# MC21R01_uC_GPIO.net
KiCad netlist of a schematic drawn in Altium Designer
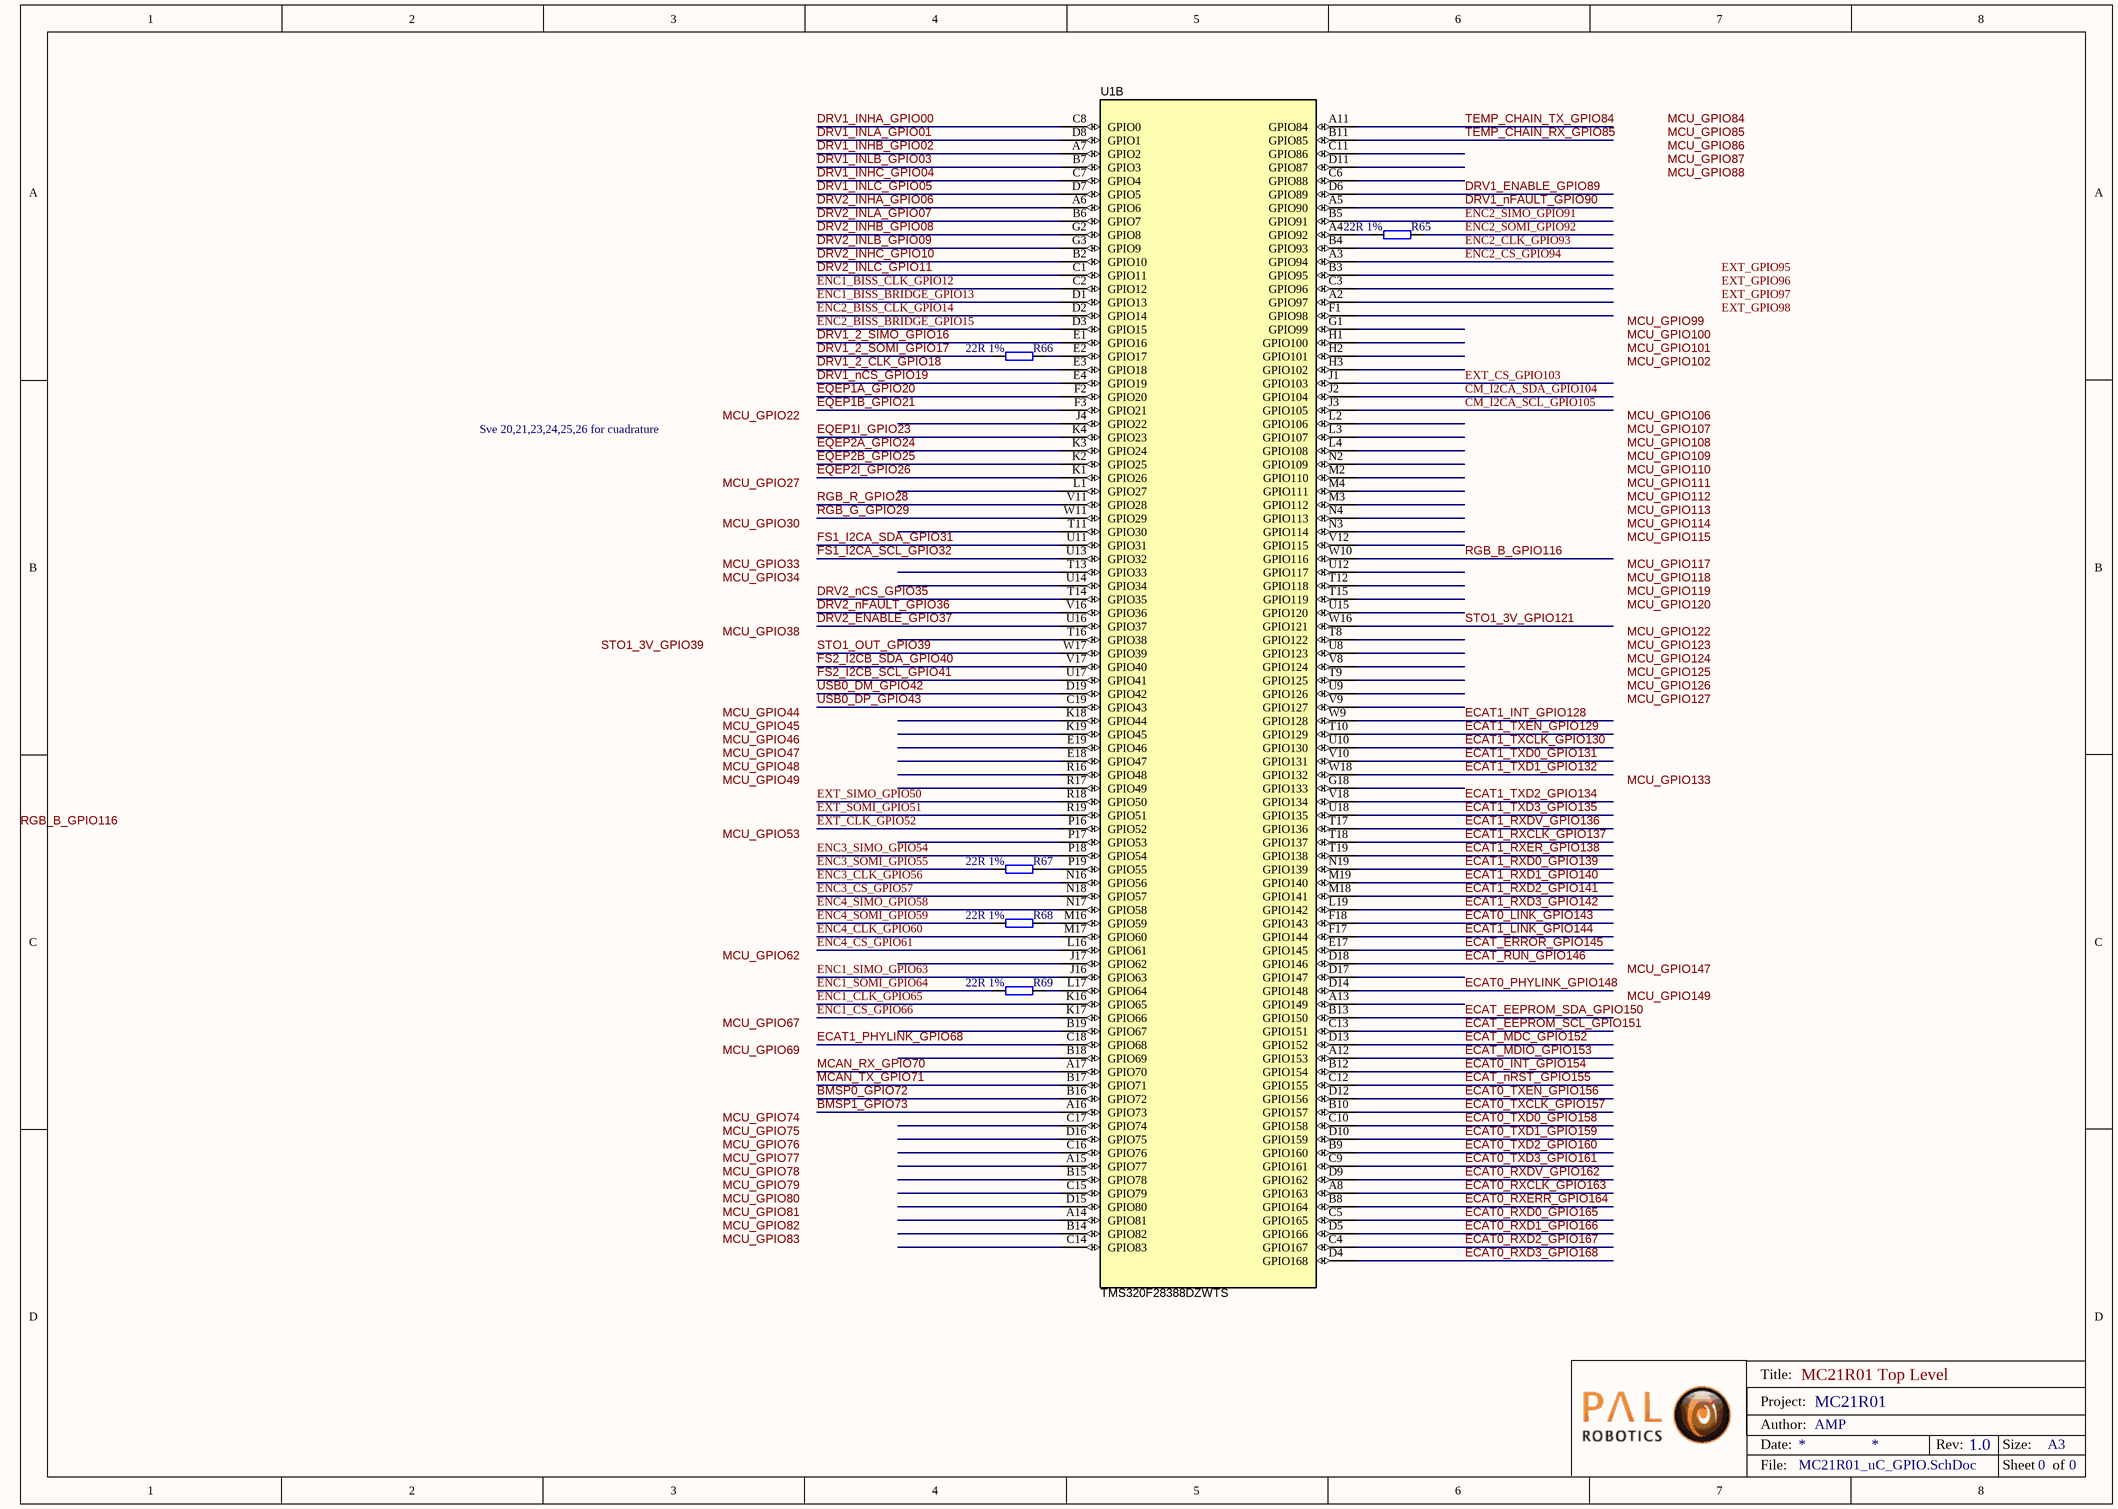
[diagram p0: MC21R01_uC_GPIO.SchDoc]

(export (version "E")
  (design (tool "Eeschema 10.0.6"))
  (components
    (comp (ref "R65")
      (value "22R 1%")
      (footprint "0402 SMD rESISTOR")
      (description "22R/50V 1% 0402 63mW SMD Resistor")
      (libsource (lib "PAL_Resistors") (part "22R/50V 1% 0402 63mW"))
    )
    (comp (ref "R66")
      (value "22R 1%")
      (footprint "0402 SMD rESISTOR")
      (description "22R/50V 1% 0402 63mW SMD Resistor")
      (libsource (lib "PAL_Resistors") (part "22R/50V 1% 0402 63mW"))
    )
    (comp (ref "R67")
      (value "22R 1%")
      (footprint "0402 SMD rESISTOR")
      (description "22R/50V 1% 0402 63mW SMD Resistor")
      (libsource (lib "PAL_Resistors") (part "22R/50V 1% 0402 63mW"))
    )
    (comp (ref "R68")
      (value "22R 1%")
      (footprint "0402 SMD rESISTOR")
      (description "22R/50V 1% 0402 63mW SMD Resistor")
      (libsource (lib "PAL_Resistors") (part "22R/50V 1% 0402 63mW"))
    )
    (comp (ref "R69")
      (value "22R 1%")
      (footprint "0402 SMD rESISTOR")
      (description "22R/50V 1% 0402 63mW SMD Resistor")
      (libsource (lib "PAL_Resistors") (part "22R/50V 1% 0402 63mW"))
    )
    (comp (ref "U1")
      (value "TMS320F28388DZWTS")
      (footprint "ZWT0337A")
      (description "TMS320F28388DZWTS, ZWT0337A (NFBGA-337)")
      (fields
        (field (name "MANUFACTURER") "Texas Instruments")
        (field (name "PARTNUMBER") "TMS320F28388DZWTS")
      )
      (libsource (lib "PAL_devices") (part "TMS320F28388"))
    )
  )
  (nets
    (net (code "1") (name "/BMSP0_GPIO72") (class "Default")
      (node (ref "U1") (pin "B16") (pinfunction "GPIO72_B16") (pintype "bidirectional"))
    )
    (net (code "2") (name "/BMSP1_GPIO73") (class "Default")
      (node (ref "U1") (pin "A16") (pinfunction "GPIO73_A16") (pintype "bidirectional"))
    )
    (net (code "3") (name "/CM_I2CA_SCL_GPIO105") (class "Default")
      (node (ref "U1") (pin "J3") (pinfunction "GPIO105_J3") (pintype "bidirectional"))
    )
    (net (code "4") (name "/CM_I2CA_SDA_GPIO104") (class "Default")
      (node (ref "U1") (pin "J2") (pinfunction "GPIO104_J2") (pintype "bidirectional"))
    )
    (net (code "5") (name "/DRV1_2_CLK_GPIO18") (class "Default")
      (node (ref "U1") (pin "E3") (pinfunction "GPIO18_E3") (pintype "bidirectional"))
    )
    (net (code "6") (name "/DRV1_2_SIMO_GPIO16") (class "Default")
      (node (ref "U1") (pin "E1") (pinfunction "GPIO16_E1") (pintype "bidirectional"))
    )
    (net (code "7") (name "/DRV1_2_SOMI_GPIO17") (class "Default")
      (node (ref "R66") (pin "2") (pinfunction "2_2") (pintype "passive"))
    )
    (net (code "8") (name "/DRV1_ENABLE_GPIO89") (class "Default")
      (node (ref "U1") (pin "D6") (pinfunction "GPIO89_D6") (pintype "bidirectional"))
    )
    (net (code "9") (name "/DRV1_INHA_GPIO00") (class "Default")
      (node (ref "U1") (pin "C8") (pinfunction "GPIO0_C8") (pintype "bidirectional"))
    )
    (net (code "10") (name "/DRV1_INHB_GPIO02") (class "Default")
      (node (ref "U1") (pin "A7") (pinfunction "GPIO2_A7") (pintype "bidirectional"))
    )
    (net (code "11") (name "/DRV1_INHC_GPIO04") (class "Default")
      (node (ref "U1") (pin "C7") (pinfunction "GPIO4_C7") (pintype "bidirectional"))
    )
    (net (code "12") (name "/DRV1_INLA_GPIO01") (class "Default")
      (node (ref "U1") (pin "D8") (pinfunction "GPIO1_D8") (pintype "bidirectional"))
    )
    (net (code "13") (name "/DRV1_INLB_GPIO03") (class "Default")
      (node (ref "U1") (pin "B7") (pinfunction "GPIO3_B7") (pintype "bidirectional"))
    )
    (net (code "14") (name "/DRV1_INLC_GPIO05") (class "Default")
      (node (ref "U1") (pin "D7") (pinfunction "GPIO5_D7") (pintype "bidirectional"))
    )
    (net (code "15") (name "/DRV1_nCS_GPIO19") (class "Default")
      (node (ref "U1") (pin "E4") (pinfunction "GPIO19_E4") (pintype "bidirectional"))
    )
    (net (code "16") (name "/DRV1_nFAULT_GPIO90") (class "Default")
      (node (ref "U1") (pin "A5") (pinfunction "GPIO90_A5") (pintype "bidirectional"))
    )
    (net (code "17") (name "/DRV2_ENABLE_GPIO37") (class "Default")
      (node (ref "U1") (pin "U16") (pinfunction "GPIO37_U16") (pintype "bidirectional"))
    )
    (net (code "18") (name "/DRV2_INHA_GPIO06") (class "Default")
      (node (ref "U1") (pin "A6") (pinfunction "GPIO6_A6") (pintype "bidirectional"))
    )
    (net (code "19") (name "/DRV2_INHB_GPIO08") (class "Default")
      (node (ref "U1") (pin "G2") (pinfunction "GPIO8_G2") (pintype "bidirectional"))
    )
    (net (code "20") (name "/DRV2_INHC_GPIO10") (class "Default")
      (node (ref "U1") (pin "B2") (pinfunction "GPIO10_B2") (pintype "bidirectional"))
    )
    (net (code "21") (name "/DRV2_INLA_GPIO07") (class "Default")
      (node (ref "U1") (pin "B6") (pinfunction "GPIO7_B6") (pintype "bidirectional"))
    )
    (net (code "22") (name "/DRV2_INLB_GPIO09") (class "Default")
      (node (ref "U1") (pin "G3") (pinfunction "GPIO9_G3") (pintype "bidirectional"))
    )
    (net (code "23") (name "/DRV2_INLC_GPIO11") (class "Default")
      (node (ref "U1") (pin "C1") (pinfunction "GPIO11_C1") (pintype "bidirectional"))
    )
    (net (code "24") (name "/DRV2_nCS_GPIO35") (class "Default")
      (node (ref "U1") (pin "T14") (pinfunction "GPIO35_T14") (pintype "bidirectional"))
    )
    (net (code "25") (name "/DRV2_nFAULT_GPIO36") (class "Default")
      (node (ref "U1") (pin "V16") (pinfunction "GPIO36_V16") (pintype "bidirectional"))
    )
    (net (code "26") (name "/ECAT0_INT_GPIO154") (class "Default")
      (node (ref "U1") (pin "B12") (pinfunction "GPIO154_B12") (pintype "bidirectional"))
    )
    (net (code "27") (name "/ECAT0_LINK_GPIO143") (class "Default")
      (node (ref "U1") (pin "F18") (pinfunction "GPIO143_F18") (pintype "bidirectional"))
    )
    (net (code "28") (name "/ECAT0_PHYLINK_GPIO148") (class "Default")
      (node (ref "U1") (pin "D14") (pinfunction "GPIO148_D14") (pintype "bidirectional"))
    )
    (net (code "29") (name "/ECAT0_RXCLK_GPIO163") (class "Default")
      (node (ref "U1") (pin "A8") (pinfunction "GPIO163_A8") (pintype "bidirectional"))
    )
    (net (code "30") (name "/ECAT0_RXD0_GPIO165") (class "Default")
      (node (ref "U1") (pin "C5") (pinfunction "GPIO165_C5") (pintype "bidirectional"))
    )
    (net (code "31") (name "/ECAT0_RXD1_GPIO166") (class "Default")
      (node (ref "U1") (pin "D5") (pinfunction "GPIO166_D5") (pintype "bidirectional"))
    )
    (net (code "32") (name "/ECAT0_RXD2_GPIO167") (class "Default")
      (node (ref "U1") (pin "C4") (pinfunction "GPIO167_C4") (pintype "bidirectional"))
    )
    (net (code "33") (name "/ECAT0_RXD3_GPIO168") (class "Default")
      (node (ref "U1") (pin "D4") (pinfunction "GPIO168_D4") (pintype "bidirectional"))
    )
    (net (code "34") (name "/ECAT0_RXDV_GPIO162") (class "Default")
      (node (ref "U1") (pin "D9") (pinfunction "GPIO162_D9") (pintype "bidirectional"))
    )
    (net (code "35") (name "/ECAT0_RXERR_GPIO164") (class "Default")
      (node (ref "U1") (pin "B8") (pinfunction "GPIO164_B8") (pintype "bidirectional"))
    )
    (net (code "36") (name "/ECAT0_TXCLK_GPIO157") (class "Default")
      (node (ref "U1") (pin "B10") (pinfunction "GPIO157_B10") (pintype "bidirectional"))
    )
    (net (code "37") (name "/ECAT0_TXD0_GPIO158") (class "Default")
      (node (ref "U1") (pin "C10") (pinfunction "GPIO158_C10") (pintype "bidirectional"))
    )
    (net (code "38") (name "/ECAT0_TXD1_GPIO159") (class "Default")
      (node (ref "U1") (pin "D10") (pinfunction "GPIO159_D10") (pintype "bidirectional"))
    )
    (net (code "39") (name "/ECAT0_TXD2_GPIO160") (class "Default")
      (node (ref "U1") (pin "B9") (pinfunction "GPIO160_B9") (pintype "bidirectional"))
    )
    (net (code "40") (name "/ECAT0_TXD3_GPIO161") (class "Default")
      (node (ref "U1") (pin "C9") (pinfunction "GPIO161_C9") (pintype "bidirectional"))
    )
    (net (code "41") (name "/ECAT0_TXEN_GPIO156") (class "Default")
      (node (ref "U1") (pin "D12") (pinfunction "GPIO156_D12") (pintype "bidirectional"))
    )
    (net (code "42") (name "/ECAT1_INT_GPIO128") (class "Default")
      (node (ref "U1") (pin "W9") (pinfunction "GPIO128_W9") (pintype "bidirectional"))
    )
    (net (code "43") (name "/ECAT1_LINK_GPIO144") (class "Default")
      (node (ref "U1") (pin "F17") (pinfunction "GPIO144_F17") (pintype "bidirectional"))
    )
    (net (code "44") (name "/ECAT1_PHYLINK_GPIO68") (class "Default")
      (node (ref "U1") (pin "C18") (pinfunction "GPIO68_C18") (pintype "bidirectional"))
    )
    (net (code "45") (name "/ECAT1_RXCLK_GPIO137") (class "Default")
      (node (ref "U1") (pin "T18") (pinfunction "GPIO137_T18") (pintype "bidirectional"))
    )
    (net (code "46") (name "/ECAT1_RXD0_GPIO139") (class "Default")
      (node (ref "U1") (pin "N19") (pinfunction "GPIO139_N19") (pintype "bidirectional"))
    )
    (net (code "47") (name "/ECAT1_RXD1_GPIO140") (class "Default")
      (node (ref "U1") (pin "M19") (pinfunction "GPIO140_M19") (pintype "bidirectional"))
    )
    (net (code "48") (name "/ECAT1_RXD2_GPIO141") (class "Default")
      (node (ref "U1") (pin "M18") (pinfunction "GPIO141_M18") (pintype "bidirectional"))
    )
    (net (code "49") (name "/ECAT1_RXD3_GPIO142") (class "Default")
      (node (ref "U1") (pin "L19") (pinfunction "GPIO142_L19") (pintype "bidirectional"))
    )
    (net (code "50") (name "/ECAT1_RXDV_GPIO136") (class "Default")
      (node (ref "U1") (pin "T17") (pinfunction "GPIO136_T17") (pintype "bidirectional"))
    )
    (net (code "51") (name "/ECAT1_RXER_GPIO138") (class "Default")
      (node (ref "U1") (pin "T19") (pinfunction "GPIO138_T19") (pintype "bidirectional"))
    )
    (net (code "52") (name "/ECAT1_TXCLK_GPIO130") (class "Default")
      (node (ref "U1") (pin "U10") (pinfunction "GPIO130_U10") (pintype "bidirectional"))
    )
    (net (code "53") (name "/ECAT1_TXD0_GPIO131") (class "Default")
      (node (ref "U1") (pin "V10") (pinfunction "GPIO131_V10") (pintype "bidirectional"))
    )
    (net (code "54") (name "/ECAT1_TXD1_GPIO132") (class "Default")
      (node (ref "U1") (pin "W18") (pinfunction "GPIO132_W18") (pintype "bidirectional"))
    )
    (net (code "55") (name "/ECAT1_TXD2_GPIO134") (class "Default")
      (node (ref "U1") (pin "V18") (pinfunction "GPIO134_V18") (pintype "bidirectional"))
    )
    (net (code "56") (name "/ECAT1_TXD3_GPIO135") (class "Default")
      (node (ref "U1") (pin "U18") (pinfunction "GPIO135_U18") (pintype "bidirectional"))
    )
    (net (code "57") (name "/ECAT1_TXEN_GPIO129") (class "Default")
      (node (ref "U1") (pin "T10") (pinfunction "GPIO129_T10") (pintype "bidirectional"))
    )
    (net (code "58") (name "/ECAT_EEPROM_SCL_GPIO151") (class "Default")
      (node (ref "U1") (pin "C13") (pinfunction "GPIO151_C13") (pintype "bidirectional"))
    )
    (net (code "59") (name "/ECAT_EEPROM_SDA_GPIO150") (class "Default")
      (node (ref "U1") (pin "B13") (pinfunction "GPIO150_B13") (pintype "bidirectional"))
    )
    (net (code "60") (name "/ECAT_ERROR_GPIO145") (class "Default")
      (node (ref "U1") (pin "E17") (pinfunction "GPIO145_E17") (pintype "bidirectional"))
    )
    (net (code "61") (name "/ECAT_MDC_GPIO152") (class "Default")
      (node (ref "U1") (pin "D13") (pinfunction "GPIO152_D13") (pintype "bidirectional"))
    )
    (net (code "62") (name "/ECAT_MDIO_GPIO153") (class "Default")
      (node (ref "U1") (pin "A12") (pinfunction "GPIO153_A12") (pintype "bidirectional"))
    )
    (net (code "63") (name "/ECAT_RUN_GPIO146") (class "Default")
      (node (ref "U1") (pin "D18") (pinfunction "GPIO146_D18") (pintype "bidirectional"))
    )
    (net (code "64") (name "/ECAT_nRST_GPIO155") (class "Default")
      (node (ref "U1") (pin "C12") (pinfunction "GPIO155_C12") (pintype "bidirectional"))
    )
    (net (code "65") (name "/ENC1_BISS_BRIDGE_GPIO13") (class "Default")
      (node (ref "U1") (pin "D1") (pinfunction "GPIO13_D1") (pintype "bidirectional"))
    )
    (net (code "66") (name "/ENC1_BISS_CLK_GPIO12") (class "Default")
      (node (ref "U1") (pin "C2") (pinfunction "GPIO12_C2") (pintype "bidirectional"))
    )
    (net (code "67") (name "/ENC1_CLK_GPIO65") (class "Default")
      (node (ref "U1") (pin "K16") (pinfunction "GPIO65_K16") (pintype "bidirectional"))
    )
    (net (code "68") (name "/ENC1_CS_GPIO66") (class "Default")
      (node (ref "U1") (pin "K17") (pinfunction "GPIO66_K17") (pintype "bidirectional"))
    )
    (net (code "69") (name "/ENC1_SIMO_GPIO63") (class "Default")
      (node (ref "U1") (pin "J16") (pinfunction "GPIO63_J16") (pintype "bidirectional"))
    )
    (net (code "70") (name "/ENC1_SOMI_GPIO64") (class "Default")
      (node (ref "R69") (pin "2") (pinfunction "2_2") (pintype "passive"))
    )
    (net (code "71") (name "/ENC2_BISS_BRIDGE_GPIO15") (class "Default")
      (node (ref "U1") (pin "D3") (pinfunction "GPIO15_D3") (pintype "bidirectional"))
    )
    (net (code "72") (name "/ENC2_BISS_CLK_GPIO14") (class "Default")
      (node (ref "U1") (pin "D2") (pinfunction "GPIO14_D2") (pintype "bidirectional"))
    )
    (net (code "73") (name "/ENC2_CLK_GPIO93") (class "Default")
      (node (ref "U1") (pin "B4") (pinfunction "GPIO93_B4") (pintype "bidirectional"))
    )
    (net (code "74") (name "/ENC2_CS_GPIO94") (class "Default")
      (node (ref "U1") (pin "A3") (pinfunction "GPIO94_A3") (pintype "bidirectional"))
    )
    (net (code "75") (name "/ENC2_SIMO_GPIO91") (class "Default")
      (node (ref "U1") (pin "B5") (pinfunction "GPIO91_B5") (pintype "bidirectional"))
    )
    (net (code "76") (name "/ENC2_SOMI_GPIO92") (class "Default")
      (node (ref "R65") (pin "1") (pinfunction "1_1") (pintype "passive"))
    )
    (net (code "77") (name "/ENC3_CLK_GPIO56") (class "Default")
      (node (ref "U1") (pin "N16") (pinfunction "GPIO56_N16") (pintype "bidirectional"))
    )
    (net (code "78") (name "/ENC3_CS_GPIO57") (class "Default")
      (node (ref "U1") (pin "N18") (pinfunction "GPIO57_N18") (pintype "bidirectional"))
    )
    (net (code "79") (name "/ENC3_SIMO_GPIO54") (class "Default")
      (node (ref "U1") (pin "P18") (pinfunction "GPIO54_P18") (pintype "bidirectional"))
    )
    (net (code "80") (name "/ENC3_SOMI_GPIO55") (class "Default")
      (node (ref "R67") (pin "2") (pinfunction "2_2") (pintype "passive"))
    )
    (net (code "81") (name "/ENC4_CLK_GPIO60") (class "Default")
      (node (ref "U1") (pin "M17") (pinfunction "GPIO60_M17") (pintype "bidirectional"))
    )
    (net (code "82") (name "/ENC4_CS_GPIO61") (class "Default")
      (node (ref "U1") (pin "L16") (pinfunction "GPIO61_L16") (pintype "bidirectional"))
    )
    (net (code "83") (name "/ENC4_SIMO_GPIO58") (class "Default")
      (node (ref "U1") (pin "N17") (pinfunction "GPIO58_N17") (pintype "bidirectional"))
    )
    (net (code "84") (name "/ENC4_SOMI_GPIO59") (class "Default")
      (node (ref "R68") (pin "2") (pinfunction "2_2") (pintype "passive"))
    )
    (net (code "85") (name "/EQEP1A_GPIO20") (class "Default")
      (node (ref "U1") (pin "F2") (pinfunction "GPIO20_F2") (pintype "bidirectional"))
    )
    (net (code "86") (name "/EQEP1B_GPIO21") (class "Default")
      (node (ref "U1") (pin "F3") (pinfunction "GPIO21_F3") (pintype "bidirectional"))
    )
    (net (code "87") (name "/EQEP1I_GPIO23") (class "Default")
      (node (ref "U1") (pin "K4") (pinfunction "GPIO23_K4") (pintype "bidirectional"))
    )
    (net (code "88") (name "/EQEP2A_GPIO24") (class "Default")
      (node (ref "U1") (pin "K3") (pinfunction "GPIO24_K3") (pintype "bidirectional"))
    )
    (net (code "89") (name "/EQEP2B_GPIO25") (class "Default")
      (node (ref "U1") (pin "K2") (pinfunction "GPIO25_K2") (pintype "bidirectional"))
    )
    (net (code "90") (name "/EQEP2I_GPIO26") (class "Default")
      (node (ref "U1") (pin "K1") (pinfunction "GPIO26_K1") (pintype "bidirectional"))
    )
    (net (code "91") (name "/EXT_CLK_GPIO52") (class "Default")
      (node (ref "U1") (pin "P16") (pinfunction "GPIO52_P16") (pintype "bidirectional"))
    )
    (net (code "92") (name "/EXT_CS_GPIO103") (class "Default")
      (node (ref "U1") (pin "J1") (pinfunction "GPIO103_J1") (pintype "bidirectional"))
    )
    (net (code "97") (name "/EXT_SIMO_GPIO50") (class "Default")
      (node (ref "U1") (pin "R18") (pinfunction "GPIO50_R18") (pintype "bidirectional"))
    )
    (net (code "98") (name "/EXT_SOMI_GPIO51") (class "Default")
      (node (ref "U1") (pin "R19") (pinfunction "GPIO51_R19") (pintype "bidirectional"))
    )
    (net (code "99") (name "/FS1_I2CA_SCL_GPIO32") (class "Default")
      (node (ref "U1") (pin "U13") (pinfunction "GPIO32_U13") (pintype "bidirectional"))
    )
    (net (code "100") (name "/FS1_I2CA_SDA_GPIO31") (class "Default")
      (node (ref "U1") (pin "U11") (pinfunction "GPIO31_U11") (pintype "bidirectional"))
    )
    (net (code "101") (name "/FS2_I2CB_SCL_GPIO41") (class "Default")
      (node (ref "U1") (pin "U17") (pinfunction "GPIO41_U17") (pintype "bidirectional"))
    )
    (net (code "102") (name "/FS2_I2CB_SDA_GPIO40") (class "Default")
      (node (ref "U1") (pin "V17") (pinfunction "GPIO40_V17") (pintype "bidirectional"))
    )
    (net (code "103") (name "/MCAN_RX_GPIO70") (class "Default")
      (node (ref "U1") (pin "A17") (pinfunction "GPIO70_A17") (pintype "bidirectional"))
    )
    (net (code "104") (name "/MCAN_TX_GPIO71") (class "Default")
      (node (ref "U1") (pin "B17") (pinfunction "GPIO71_B17") (pintype "bidirectional"))
    )
    (net (code "163") (name "/RGB_B_GPIO116") (class "Default")
      (node (ref "U1") (pin "W10") (pinfunction "GPIO116_W10") (pintype "bidirectional"))
    )
    (net (code "164") (name "/RGB_G_GPIO29") (class "Default")
      (node (ref "U1") (pin "W11") (pinfunction "GPIO29_W11") (pintype "bidirectional"))
    )
    (net (code "165") (name "/RGB_R_GPIO28") (class "Default")
      (node (ref "U1") (pin "V11") (pinfunction "GPIO28_V11") (pintype "bidirectional"))
    )
    (net (code "167") (name "/STO1_3V_GPIO121") (class "Default")
      (node (ref "U1") (pin "W16") (pinfunction "GPIO121_W16") (pintype "bidirectional"))
    )
    (net (code "168") (name "/STO1_OUT_GPIO39") (class "Default")
      (node (ref "U1") (pin "W17") (pinfunction "GPIO39_W17") (pintype "bidirectional"))
    )
    (net (code "169") (name "/TEMP_CHAIN_RX_GPIO85") (class "Default")
      (node (ref "U1") (pin "B11") (pinfunction "GPIO85_B11") (pintype "bidirectional"))
    )
    (net (code "170") (name "/TEMP_CHAIN_TX_GPIO84") (class "Default")
      (node (ref "U1") (pin "A11") (pinfunction "GPIO84_A11") (pintype "bidirectional"))
    )
    (net (code "171") (name "/USB0_DM_GPIO42") (class "Default")
      (node (ref "U1") (pin "D19") (pinfunction "GPIO42_D19") (pintype "bidirectional"))
    )
    (net (code "172") (name "/USB0_DP_GPIO43") (class "Default")
      (node (ref "U1") (pin "C19") (pinfunction "GPIO43_C19") (pintype "bidirectional"))
    )
    (net (code "173") (name "Net-(U1B-GPIO17)") (class "Default")
      (node (ref "R66") (pin "1") (pinfunction "1_1") (pintype "passive"))
      (node (ref "U1") (pin "E2") (pinfunction "GPIO17_E2") (pintype "bidirectional"))
    )
    (net (code "174") (name "Net-(U1B-GPIO55)") (class "Default")
      (node (ref "R67") (pin "1") (pinfunction "1_1") (pintype "passive"))
      (node (ref "U1") (pin "P19") (pinfunction "GPIO55_P19") (pintype "bidirectional"))
    )
    (net (code "175") (name "Net-(U1B-GPIO59)") (class "Default")
      (node (ref "R68") (pin "1") (pinfunction "1_1") (pintype "passive"))
      (node (ref "U1") (pin "M16") (pinfunction "GPIO59_M16") (pintype "bidirectional"))
    )
    (net (code "176") (name "Net-(U1B-GPIO64)") (class "Default")
      (node (ref "R69") (pin "1") (pinfunction "1_1") (pintype "passive"))
      (node (ref "U1") (pin "L17") (pinfunction "GPIO64_L17") (pintype "bidirectional"))
    )
    (net (code "177") (name "Net-(U1B-GPIO92)") (class "Default")
      (node (ref "R65") (pin "2") (pinfunction "2_2") (pintype "passive"))
      (node (ref "U1") (pin "A4") (pinfunction "GPIO92_A4") (pintype "bidirectional"))
    )
    (net (code "178") (name "unconnected-(U1B-GPIO22-PadJ4)") (class "Default")
      (node (ref "U1") (pin "J4") (pinfunction "GPIO22_J4") (pintype "bidirectional"))
    )
    (net (code "179") (name "unconnected-(U1B-GPIO27-PadL1)") (class "Default")
      (node (ref "U1") (pin "L1") (pinfunction "GPIO27_L1") (pintype "bidirectional"))
    )
    (net (code "180") (name "unconnected-(U1B-GPIO30-PadT11)") (class "Default")
      (node (ref "U1") (pin "T11") (pinfunction "GPIO30_T11") (pintype "bidirectional"))
    )
    (net (code "181") (name "unconnected-(U1B-GPIO33-PadT13)") (class "Default")
      (node (ref "U1") (pin "T13") (pinfunction "GPIO33_T13") (pintype "bidirectional"))
    )
    (net (code "182") (name "unconnected-(U1B-GPIO34-PadU14)") (class "Default")
      (node (ref "U1") (pin "U14") (pinfunction "GPIO34_U14") (pintype "bidirectional"))
    )
    (net (code "183") (name "unconnected-(U1B-GPIO38-PadT16)") (class "Default")
      (node (ref "U1") (pin "T16") (pinfunction "GPIO38_T16") (pintype "bidirectional"))
    )
    (net (code "184") (name "unconnected-(U1B-GPIO44-PadK18)") (class "Default")
      (node (ref "U1") (pin "K18") (pinfunction "GPIO44_K18") (pintype "bidirectional"))
    )
    (net (code "185") (name "unconnected-(U1B-GPIO45-PadK19)") (class "Default")
      (node (ref "U1") (pin "K19") (pinfunction "GPIO45_K19") (pintype "bidirectional"))
    )
    (net (code "186") (name "unconnected-(U1B-GPIO46-PadE19)") (class "Default")
      (node (ref "U1") (pin "E19") (pinfunction "GPIO46_E19") (pintype "bidirectional"))
    )
    (net (code "187") (name "unconnected-(U1B-GPIO47-PadE18)") (class "Default")
      (node (ref "U1") (pin "E18") (pinfunction "GPIO47_E18") (pintype "bidirectional"))
    )
    (net (code "188") (name "unconnected-(U1B-GPIO48-PadR16)") (class "Default")
      (node (ref "U1") (pin "R16") (pinfunction "GPIO48_R16") (pintype "bidirectional"))
    )
    (net (code "189") (name "unconnected-(U1B-GPIO49-PadR17)") (class "Default")
      (node (ref "U1") (pin "R17") (pinfunction "GPIO49_R17") (pintype "bidirectional"))
    )
    (net (code "190") (name "unconnected-(U1B-GPIO53-PadP17)") (class "Default")
      (node (ref "U1") (pin "P17") (pinfunction "GPIO53_P17") (pintype "bidirectional"))
    )
    (net (code "191") (name "unconnected-(U1B-GPIO62-PadJ17)") (class "Default")
      (node (ref "U1") (pin "J17") (pinfunction "GPIO62_J17") (pintype "bidirectional"))
    )
    (net (code "192") (name "unconnected-(U1B-GPIO67-PadB19)") (class "Default")
      (node (ref "U1") (pin "B19") (pinfunction "GPIO67_B19") (pintype "bidirectional"))
    )
    (net (code "193") (name "unconnected-(U1B-GPIO69-PadB18)") (class "Default")
      (node (ref "U1") (pin "B18") (pinfunction "GPIO69_B18") (pintype "bidirectional"))
    )
    (net (code "194") (name "unconnected-(U1B-GPIO74-PadC17)") (class "Default")
      (node (ref "U1") (pin "C17") (pinfunction "GPIO74_C17") (pintype "bidirectional"))
    )
    (net (code "195") (name "unconnected-(U1B-GPIO75-PadD16)") (class "Default")
      (node (ref "U1") (pin "D16") (pinfunction "GPIO75_D16") (pintype "bidirectional"))
    )
    (net (code "196") (name "unconnected-(U1B-GPIO76-PadC16)") (class "Default")
      (node (ref "U1") (pin "C16") (pinfunction "GPIO76_C16") (pintype "bidirectional"))
    )
    (net (code "197") (name "unconnected-(U1B-GPIO77-PadA15)") (class "Default")
      (node (ref "U1") (pin "A15") (pinfunction "GPIO77_A15") (pintype "bidirectional"))
    )
    (net (code "198") (name "unconnected-(U1B-GPIO78-PadB15)") (class "Default")
      (node (ref "U1") (pin "B15") (pinfunction "GPIO78_B15") (pintype "bidirectional"))
    )
    (net (code "199") (name "unconnected-(U1B-GPIO79-PadC15)") (class "Default")
      (node (ref "U1") (pin "C15") (pinfunction "GPIO79_C15") (pintype "bidirectional"))
    )
    (net (code "200") (name "unconnected-(U1B-GPIO80-PadD15)") (class "Default")
      (node (ref "U1") (pin "D15") (pinfunction "GPIO80_D15") (pintype "bidirectional"))
    )
    (net (code "201") (name "unconnected-(U1B-GPIO81-PadA14)") (class "Default")
      (node (ref "U1") (pin "A14") (pinfunction "GPIO81_A14") (pintype "bidirectional"))
    )
    (net (code "202") (name "unconnected-(U1B-GPIO82-PadB14)") (class "Default")
      (node (ref "U1") (pin "B14") (pinfunction "GPIO82_B14") (pintype "bidirectional"))
    )
    (net (code "203") (name "unconnected-(U1B-GPIO83-PadC14)") (class "Default")
      (node (ref "U1") (pin "C14") (pinfunction "GPIO83_C14") (pintype "bidirectional"))
    )
    (net (code "204") (name "unconnected-(U1B-GPIO86-PadC11)") (class "Default")
      (node (ref "U1") (pin "C11") (pinfunction "GPIO86_C11") (pintype "bidirectional"))
    )
    (net (code "205") (name "unconnected-(U1B-GPIO87-PadD11)") (class "Default")
      (node (ref "U1") (pin "D11") (pinfunction "GPIO87_D11") (pintype "bidirectional"))
    )
    (net (code "206") (name "unconnected-(U1B-GPIO88-PadC6)") (class "Default")
      (node (ref "U1") (pin "C6") (pinfunction "GPIO88_C6") (pintype "bidirectional"))
    )
    (net (code "207") (name "unconnected-(U1B-GPIO95-PadB3)") (class "Default")
      (node (ref "U1") (pin "B3") (pinfunction "GPIO95_B3") (pintype "bidirectional"))
    )
    (net (code "208") (name "unconnected-(U1B-GPIO96-PadC3)") (class "Default")
      (node (ref "U1") (pin "C3") (pinfunction "GPIO96_C3") (pintype "bidirectional"))
    )
    (net (code "209") (name "unconnected-(U1B-GPIO97-PadA2)") (class "Default")
      (node (ref "U1") (pin "A2") (pinfunction "GPIO97_A2") (pintype "bidirectional"))
    )
    (net (code "210") (name "unconnected-(U1B-GPIO98-PadF1)") (class "Default")
      (node (ref "U1") (pin "F1") (pinfunction "GPIO98_F1") (pintype "bidirectional"))
    )
    (net (code "211") (name "unconnected-(U1B-GPIO99-PadG1)") (class "Default")
      (node (ref "U1") (pin "G1") (pinfunction "GPIO99_G1") (pintype "bidirectional"))
    )
    (net (code "212") (name "unconnected-(U1B-GPIO100-PadH1)") (class "Default")
      (node (ref "U1") (pin "H1") (pinfunction "GPIO100_H1") (pintype "bidirectional"))
    )
    (net (code "213") (name "unconnected-(U1B-GPIO101-PadH2)") (class "Default")
      (node (ref "U1") (pin "H2") (pinfunction "GPIO101_H2") (pintype "bidirectional"))
    )
    (net (code "214") (name "unconnected-(U1B-GPIO102-PadH3)") (class "Default")
      (node (ref "U1") (pin "H3") (pinfunction "GPIO102_H3") (pintype "bidirectional"))
    )
    (net (code "215") (name "unconnected-(U1B-GPIO106-PadL2)") (class "Default")
      (node (ref "U1") (pin "L2") (pinfunction "GPIO106_L2") (pintype "bidirectional"))
    )
    (net (code "216") (name "unconnected-(U1B-GPIO107-PadL3)") (class "Default")
      (node (ref "U1") (pin "L3") (pinfunction "GPIO107_L3") (pintype "bidirectional"))
    )
    (net (code "217") (name "unconnected-(U1B-GPIO108-PadL4)") (class "Default")
      (node (ref "U1") (pin "L4") (pinfunction "GPIO108_L4") (pintype "bidirectional"))
    )
    (net (code "218") (name "unconnected-(U1B-GPIO109-PadN2)") (class "Default")
      (node (ref "U1") (pin "N2") (pinfunction "GPIO109_N2") (pintype "bidirectional"))
    )
    (net (code "219") (name "unconnected-(U1B-GPIO110-PadM2)") (class "Default")
      (node (ref "U1") (pin "M2") (pinfunction "GPIO110_M2") (pintype "bidirectional"))
    )
    (net (code "220") (name "unconnected-(U1B-GPIO111-PadM4)") (class "Default")
      (node (ref "U1") (pin "M4") (pinfunction "GPIO111_M4") (pintype "bidirectional"))
    )
    (net (code "221") (name "unconnected-(U1B-GPIO112-PadM3)") (class "Default")
      (node (ref "U1") (pin "M3") (pinfunction "GPIO112_M3") (pintype "bidirectional"))
    )
    (net (code "222") (name "unconnected-(U1B-GPIO113-PadN4)") (class "Default")
      (node (ref "U1") (pin "N4") (pinfunction "GPIO113_N4") (pintype "bidirectional"))
    )
    (net (code "223") (name "unconnected-(U1B-GPIO114-PadN3)") (class "Default")
      (node (ref "U1") (pin "N3") (pinfunction "GPIO114_N3") (pintype "bidirectional"))
    )
    (net (code "224") (name "unconnected-(U1B-GPIO115-PadV12)") (class "Default")
      (node (ref "U1") (pin "V12") (pinfunction "GPIO115_V12") (pintype "bidirectional"))
    )
    (net (code "225") (name "unconnected-(U1B-GPIO117-PadU12)") (class "Default")
      (node (ref "U1") (pin "U12") (pinfunction "GPIO117_U12") (pintype "bidirectional"))
    )
    (net (code "226") (name "unconnected-(U1B-GPIO118-PadT12)") (class "Default")
      (node (ref "U1") (pin "T12") (pinfunction "GPIO118_T12") (pintype "bidirectional"))
    )
    (net (code "227") (name "unconnected-(U1B-GPIO119-PadT15)") (class "Default")
      (node (ref "U1") (pin "T15") (pinfunction "GPIO119_T15") (pintype "bidirectional"))
    )
    (net (code "228") (name "unconnected-(U1B-GPIO120-PadU15)") (class "Default")
      (node (ref "U1") (pin "U15") (pinfunction "GPIO120_U15") (pintype "bidirectional"))
    )
    (net (code "229") (name "unconnected-(U1B-GPIO122-PadT8)") (class "Default")
      (node (ref "U1") (pin "T8") (pinfunction "GPIO122_T8") (pintype "bidirectional"))
    )
    (net (code "230") (name "unconnected-(U1B-GPIO123-PadU8)") (class "Default")
      (node (ref "U1") (pin "U8") (pinfunction "GPIO123_U8") (pintype "bidirectional"))
    )
    (net (code "231") (name "unconnected-(U1B-GPIO124-PadV8)") (class "Default")
      (node (ref "U1") (pin "V8") (pinfunction "GPIO124_V8") (pintype "bidirectional"))
    )
    (net (code "232") (name "unconnected-(U1B-GPIO125-PadT9)") (class "Default")
      (node (ref "U1") (pin "T9") (pinfunction "GPIO125_T9") (pintype "bidirectional"))
    )
    (net (code "233") (name "unconnected-(U1B-GPIO126-PadU9)") (class "Default")
      (node (ref "U1") (pin "U9") (pinfunction "GPIO126_U9") (pintype "bidirectional"))
    )
    (net (code "234") (name "unconnected-(U1B-GPIO127-PadV9)") (class "Default")
      (node (ref "U1") (pin "V9") (pinfunction "GPIO127_V9") (pintype "bidirectional"))
    )
    (net (code "235") (name "unconnected-(U1B-GPIO133-PadG18)") (class "Default")
      (node (ref "U1") (pin "G18") (pinfunction "GPIO133_G18") (pintype "bidirectional"))
    )
    (net (code "236") (name "unconnected-(U1B-GPIO147-PadD17)") (class "Default")
      (node (ref "U1") (pin "D17") (pinfunction "GPIO147_D17") (pintype "bidirectional"))
    )
    (net (code "237") (name "unconnected-(U1B-GPIO149-PadA13)") (class "Default")
      (node (ref "U1") (pin "A13") (pinfunction "GPIO149_A13") (pintype "bidirectional"))
    )
  )
)
